# Arak-Mux.net
KiCad netlist of a schematic drawn in Altium Designer
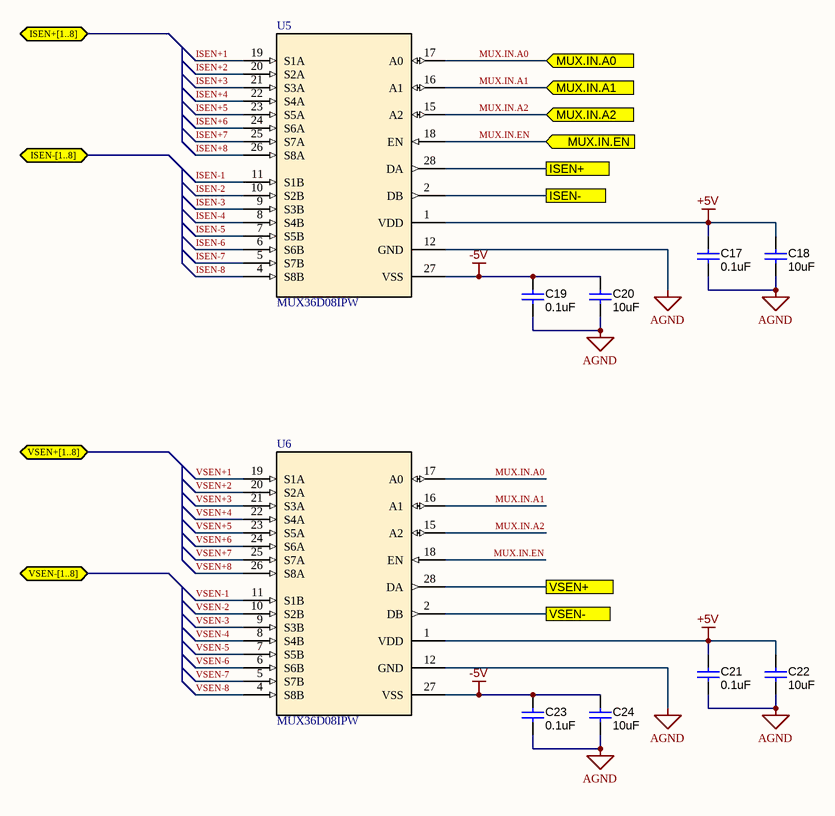
[diagram p0: Arak-Mux.SchDoc]

(export (version "E")
  (design (tool "Eeschema 10.0.6"))
  (components
    (comp (ref "C17")
      (value "Capacitor")
      (footprint "0603")
      (description "CAP, CERM, 0.1 uF, 25 V, +/- 5%, X7R, 0603")
      (fields
        (field (name "PARTNUMBER") "06033C104JAT2A")
        (field (name "VALUEDISPLAYED") "0.1uF")
        (field (name "MANUFACTURER") "AVX")
        (field (name "PUBLISHER") "Texas Instruments")
      )
      (libsource (lib "Altium Vault - TI") (part "CMP-0006752-5"))
    )
    (comp (ref "C18")
      (value "Capacitor")
      (footprint "0805_HV")
      (description "CAP, CERM, 10 uF, 10 V, +/- 10%, X7R, 0805")
      (fields
        (field (name "PARTNUMBER") "GRM21BR71A106KE51L")
        (field (name "VALUEDISPLAYED") "10uF")
        (field (name "MANUFACTURER") "MuRata")
        (field (name "PUBLISHER") "Texas Instruments")
      )
      (libsource (lib "Altium Vault - TI") (part "CMP-0008315-2"))
    )
    (comp (ref "C19")
      (value "Capacitor")
      (footprint "0603")
      (description "CAP, CERM, 0.1 uF, 25 V, +/- 5%, X7R, 0603")
      (fields
        (field (name "PARTNUMBER") "06033C104JAT2A")
        (field (name "VALUEDISPLAYED") "0.1uF")
        (field (name "MANUFACTURER") "AVX")
        (field (name "PUBLISHER") "Texas Instruments")
      )
      (libsource (lib "Altium Vault - TI") (part "CMP-0006752-5"))
    )
    (comp (ref "C20")
      (value "Capacitor")
      (footprint "0805_HV")
      (description "CAP, CERM, 10 uF, 10 V, +/- 10%, X7R, 0805")
      (fields
        (field (name "PARTNUMBER") "GRM21BR71A106KE51L")
        (field (name "VALUEDISPLAYED") "10uF")
        (field (name "MANUFACTURER") "MuRata")
        (field (name "PUBLISHER") "Texas Instruments")
      )
      (libsource (lib "Altium Vault - TI") (part "CMP-0008315-2"))
    )
    (comp (ref "C21")
      (value "Capacitor")
      (footprint "0603")
      (description "CAP, CERM, 0.1 uF, 25 V, +/- 5%, X7R, 0603")
      (fields
        (field (name "PARTNUMBER") "06033C104JAT2A")
        (field (name "VALUEDISPLAYED") "0.1uF")
        (field (name "MANUFACTURER") "AVX")
        (field (name "PUBLISHER") "Texas Instruments")
      )
      (libsource (lib "Altium Vault - TI") (part "CMP-0006752-5"))
    )
    (comp (ref "C22")
      (value "Capacitor")
      (footprint "0805_HV")
      (description "CAP, CERM, 10 uF, 10 V, +/- 10%, X7R, 0805")
      (fields
        (field (name "PARTNUMBER") "GRM21BR71A106KE51L")
        (field (name "VALUEDISPLAYED") "10uF")
        (field (name "MANUFACTURER") "MuRata")
        (field (name "PUBLISHER") "Texas Instruments")
      )
      (libsource (lib "Altium Vault - TI") (part "CMP-0008315-2"))
    )
    (comp (ref "C23")
      (value "Capacitor")
      (footprint "0603")
      (description "CAP, CERM, 0.1 uF, 25 V, +/- 5%, X7R, 0603")
      (fields
        (field (name "PARTNUMBER") "06033C104JAT2A")
        (field (name "VALUEDISPLAYED") "0.1uF")
        (field (name "MANUFACTURER") "AVX")
        (field (name "PUBLISHER") "Texas Instruments")
      )
      (libsource (lib "Altium Vault - TI") (part "CMP-0006752-5"))
    )
    (comp (ref "C24")
      (value "Capacitor")
      (footprint "0805_HV")
      (description "CAP, CERM, 10 uF, 10 V, +/- 10%, X7R, 0805")
      (fields
        (field (name "PARTNUMBER") "GRM21BR71A106KE51L")
        (field (name "VALUEDISPLAYED") "10uF")
        (field (name "MANUFACTURER") "MuRata")
        (field (name "PUBLISHER") "Texas Instruments")
      )
      (libsource (lib "Altium Vault - TI") (part "CMP-0008315-2"))
    )
    (comp (ref "U5")
      (value "MUX36D08IPW")
      (footprint "PW0016A_N")
      (description "No Description Available")
      (fields
        (field (name "PARTNUMBER") "MUX36S08IPWR")
        (field (name "MANUFACTURER") "Texas Instruments")
        (field (name "COPYRIGHT") "Copyright (C) 2018 Accelerated Designs. All rights reserved")
      )
      (libsource (lib "2020-02-03_05-08-55") (part "MUX36D08IPW"))
    )
    (comp (ref "U6")
      (value "MUX36D08IPW")
      (footprint "PW0016A_N")
      (description "No Description Available")
      (fields
        (field (name "PARTNUMBER") "MUX36S08IPWR")
        (field (name "MANUFACTURER") "Texas Instruments")
        (field (name "COPYRIGHT") "Copyright (C) 2018 Accelerated Designs. All rights reserved")
      )
      (libsource (lib "2020-02-03_05-08-55") (part "MUX36D08IPW"))
    )
  )
  (nets
    (net (code "1") (name "+5V") (class "Default")
      (node (ref "C17") (pin "1") (pinfunction "1_1") (pintype "passive"))
      (node (ref "C18") (pin "1") (pinfunction "1_1") (pintype "passive"))
      (node (ref "C21") (pin "1") (pinfunction "1_1") (pintype "passive"))
      (node (ref "C22") (pin "1") (pinfunction "1_1") (pintype "passive"))
      (node (ref "U5") (pin "1") (pinfunction "VDD_1") (pintype "power_in"))
      (node (ref "U6") (pin "1") (pinfunction "VDD_1") (pintype "power_in"))
    )
    (net (code "2") (name "-5V") (class "Default")
      (node (ref "C19") (pin "1") (pinfunction "1_1") (pintype "passive"))
      (node (ref "C20") (pin "1") (pinfunction "1_1") (pintype "passive"))
      (node (ref "C23") (pin "1") (pinfunction "1_1") (pintype "passive"))
      (node (ref "C24") (pin "1") (pinfunction "1_1") (pintype "passive"))
      (node (ref "U5") (pin "27") (pinfunction "VSS_27") (pintype "power_in"))
      (node (ref "U6") (pin "27") (pinfunction "VSS_27") (pintype "power_in"))
    )
    (net (code "3") (name "/ISEN+") (class "Default")
      (node (ref "U5") (pin "28") (pinfunction "DA_28") (pintype "output"))
    )
    (net (code "4") (name "/ISEN+1") (class "Default")
      (node (ref "U5") (pin "19") (pinfunction "S1A_19") (pintype "input"))
    )
    (net (code "5") (name "/ISEN+2") (class "Default")
      (node (ref "U5") (pin "20") (pinfunction "S2A_20") (pintype "input"))
    )
    (net (code "6") (name "/ISEN+3") (class "Default")
      (node (ref "U5") (pin "21") (pinfunction "S3A_21") (pintype "input"))
    )
    (net (code "7") (name "/ISEN+4") (class "Default")
      (node (ref "U5") (pin "22") (pinfunction "S4A_22") (pintype "input"))
    )
    (net (code "8") (name "/ISEN+5") (class "Default")
      (node (ref "U5") (pin "23") (pinfunction "S5A_23") (pintype "input"))
    )
    (net (code "9") (name "/ISEN+6") (class "Default")
      (node (ref "U5") (pin "24") (pinfunction "S6A_24") (pintype "input"))
    )
    (net (code "10") (name "/ISEN+7") (class "Default")
      (node (ref "U5") (pin "25") (pinfunction "S7A_25") (pintype "input"))
    )
    (net (code "11") (name "/ISEN+8") (class "Default")
      (node (ref "U5") (pin "26") (pinfunction "S8A_26") (pintype "input"))
    )
    (net (code "13") (name "/ISEN-") (class "Default")
      (node (ref "U5") (pin "2") (pinfunction "DB_2") (pintype "output"))
    )
    (net (code "14") (name "/ISEN-1") (class "Default")
      (node (ref "U5") (pin "11") (pinfunction "S1B_11") (pintype "input"))
    )
    (net (code "15") (name "/ISEN-2") (class "Default")
      (node (ref "U5") (pin "10") (pinfunction "S2B_10") (pintype "input"))
    )
    (net (code "16") (name "/ISEN-3") (class "Default")
      (node (ref "U5") (pin "9") (pinfunction "S3B_9") (pintype "input"))
    )
    (net (code "17") (name "/ISEN-4") (class "Default")
      (node (ref "U5") (pin "8") (pinfunction "S4B_8") (pintype "input"))
    )
    (net (code "18") (name "/ISEN-5") (class "Default")
      (node (ref "U5") (pin "7") (pinfunction "S5B_7") (pintype "input"))
    )
    (net (code "19") (name "/ISEN-6") (class "Default")
      (node (ref "U5") (pin "6") (pinfunction "S6B_6") (pintype "input"))
    )
    (net (code "20") (name "/ISEN-7") (class "Default")
      (node (ref "U5") (pin "5") (pinfunction "S7B_5") (pintype "input"))
    )
    (net (code "21") (name "/ISEN-8") (class "Default")
      (node (ref "U5") (pin "4") (pinfunction "S8B_4") (pintype "input"))
    )
    (net (code "23") (name "/MUX.IN.A0") (class "Default")
      (node (ref "U5") (pin "17") (pinfunction "A0_17") (pintype "bidirectional"))
      (node (ref "U6") (pin "17") (pinfunction "A0_17") (pintype "bidirectional"))
    )
    (net (code "24") (name "/MUX.IN.A1") (class "Default")
      (node (ref "U5") (pin "16") (pinfunction "A1_16") (pintype "bidirectional"))
      (node (ref "U6") (pin "16") (pinfunction "A1_16") (pintype "bidirectional"))
    )
    (net (code "25") (name "/MUX.IN.A2") (class "Default")
      (node (ref "U5") (pin "15") (pinfunction "A2_15") (pintype "bidirectional"))
      (node (ref "U6") (pin "15") (pinfunction "A2_15") (pintype "bidirectional"))
    )
    (net (code "26") (name "/MUX.IN.EN") (class "Default")
      (node (ref "U5") (pin "18") (pinfunction "EN_18") (pintype "input"))
      (node (ref "U6") (pin "18") (pinfunction "EN_18") (pintype "input"))
    )
    (net (code "27") (name "/VSEN+") (class "Default")
      (node (ref "U6") (pin "28") (pinfunction "DA_28") (pintype "output"))
    )
    (net (code "28") (name "/VSEN+1") (class "Default")
      (node (ref "U6") (pin "19") (pinfunction "S1A_19") (pintype "input"))
    )
    (net (code "29") (name "/VSEN+2") (class "Default")
      (node (ref "U6") (pin "20") (pinfunction "S2A_20") (pintype "input"))
    )
    (net (code "30") (name "/VSEN+3") (class "Default")
      (node (ref "U6") (pin "21") (pinfunction "S3A_21") (pintype "input"))
    )
    (net (code "31") (name "/VSEN+4") (class "Default")
      (node (ref "U6") (pin "22") (pinfunction "S4A_22") (pintype "input"))
    )
    (net (code "32") (name "/VSEN+5") (class "Default")
      (node (ref "U6") (pin "23") (pinfunction "S5A_23") (pintype "input"))
    )
    (net (code "33") (name "/VSEN+6") (class "Default")
      (node (ref "U6") (pin "24") (pinfunction "S6A_24") (pintype "input"))
    )
    (net (code "34") (name "/VSEN+7") (class "Default")
      (node (ref "U6") (pin "25") (pinfunction "S7A_25") (pintype "input"))
    )
    (net (code "35") (name "/VSEN+8") (class "Default")
      (node (ref "U6") (pin "26") (pinfunction "S8A_26") (pintype "input"))
    )
    (net (code "37") (name "/VSEN-") (class "Default")
      (node (ref "U6") (pin "2") (pinfunction "DB_2") (pintype "output"))
    )
    (net (code "38") (name "/VSEN-1") (class "Default")
      (node (ref "U6") (pin "11") (pinfunction "S1B_11") (pintype "input"))
    )
    (net (code "39") (name "/VSEN-2") (class "Default")
      (node (ref "U6") (pin "10") (pinfunction "S2B_10") (pintype "input"))
    )
    (net (code "40") (name "/VSEN-3") (class "Default")
      (node (ref "U6") (pin "9") (pinfunction "S3B_9") (pintype "input"))
    )
    (net (code "41") (name "/VSEN-4") (class "Default")
      (node (ref "U6") (pin "8") (pinfunction "S4B_8") (pintype "input"))
    )
    (net (code "42") (name "/VSEN-5") (class "Default")
      (node (ref "U6") (pin "7") (pinfunction "S5B_7") (pintype "input"))
    )
    (net (code "43") (name "/VSEN-6") (class "Default")
      (node (ref "U6") (pin "6") (pinfunction "S6B_6") (pintype "input"))
    )
    (net (code "44") (name "/VSEN-7") (class "Default")
      (node (ref "U6") (pin "5") (pinfunction "S7B_5") (pintype "input"))
    )
    (net (code "45") (name "/VSEN-8") (class "Default")
      (node (ref "U6") (pin "4") (pinfunction "S8B_4") (pintype "input"))
    )
    (net (code "47") (name "AGND") (class "Default")
      (node (ref "C17") (pin "2") (pinfunction "2_2") (pintype "passive"))
      (node (ref "C18") (pin "2") (pinfunction "2_2") (pintype "passive"))
      (node (ref "C19") (pin "2") (pinfunction "2_2") (pintype "passive"))
      (node (ref "C20") (pin "2") (pinfunction "2_2") (pintype "passive"))
      (node (ref "C21") (pin "2") (pinfunction "2_2") (pintype "passive"))
      (node (ref "C22") (pin "2") (pinfunction "2_2") (pintype "passive"))
      (node (ref "C23") (pin "2") (pinfunction "2_2") (pintype "passive"))
      (node (ref "C24") (pin "2") (pinfunction "2_2") (pintype "passive"))
      (node (ref "U5") (pin "12") (pinfunction "GND_12") (pintype "power_in"))
      (node (ref "U6") (pin "12") (pinfunction "GND_12") (pintype "power_in"))
    )
  )
)
